# Final_Bread_Proofing_Box_2020_05_10_A.net
KiCad netlist of a schematic drawn in EAGLE
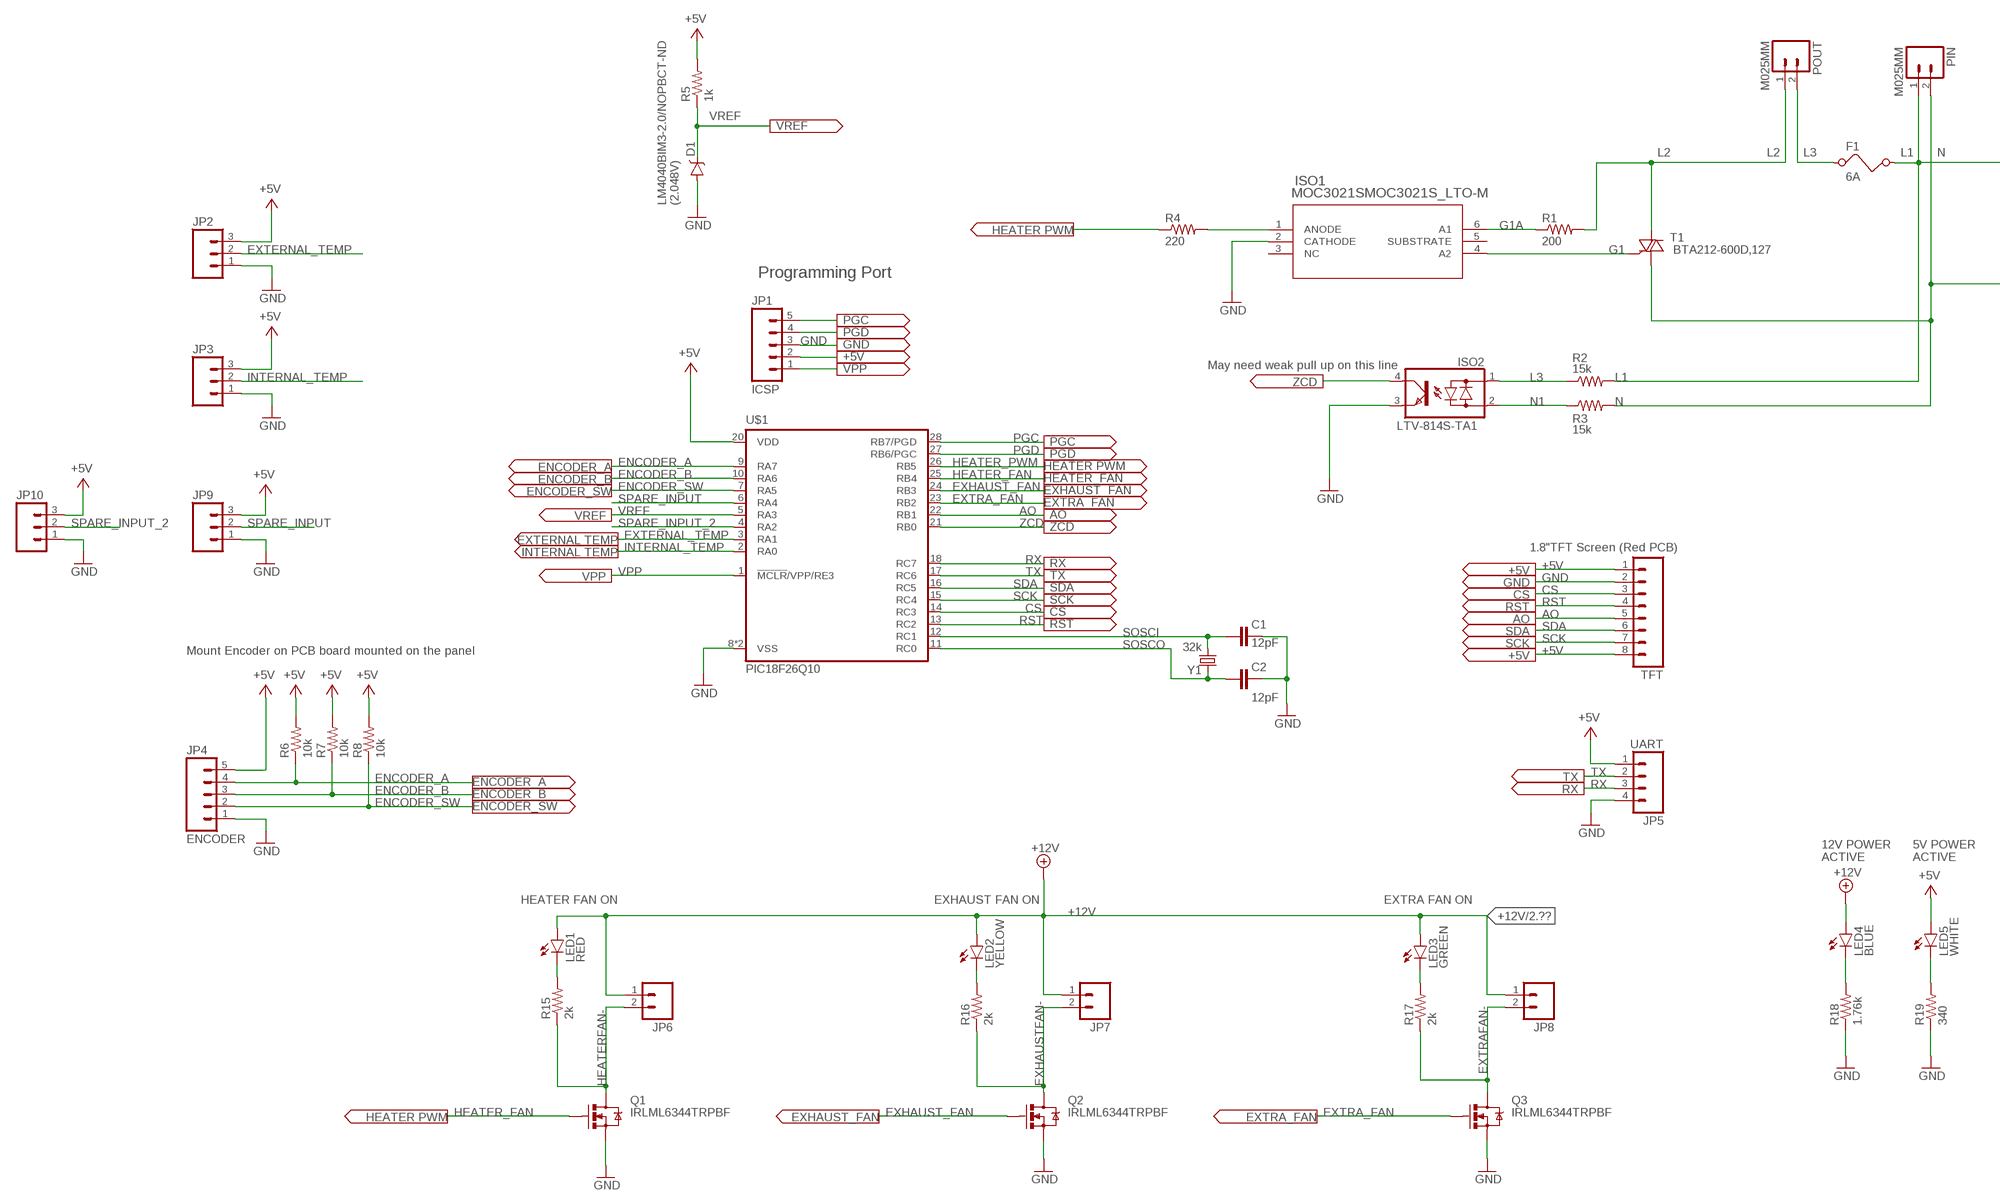
[diagram p0: schematic, sheet 1, part 1 of 2]
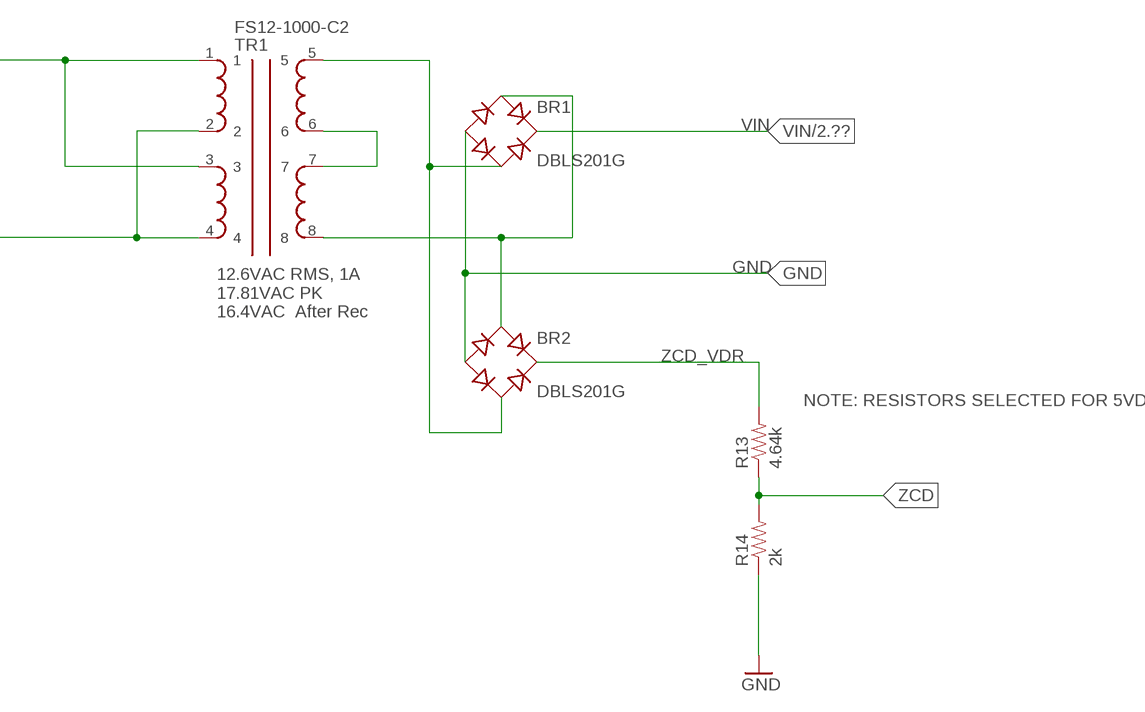
[diagram p1: schematic, sheet 1, part 2 of 2]
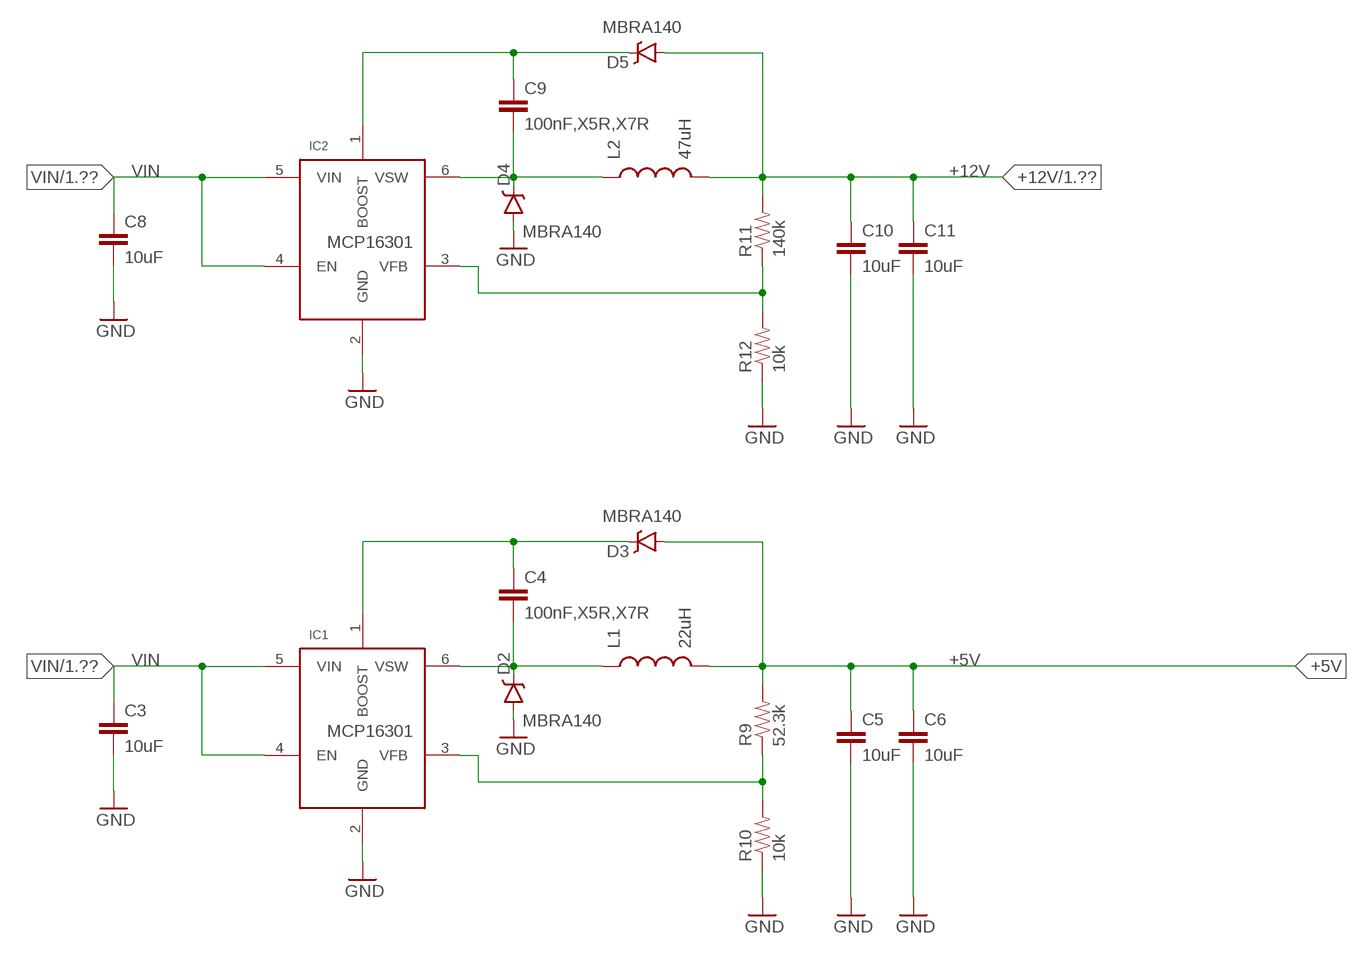
[diagram p2: schematic, sheet 2]

(export (version "E")
  (design (tool "Eeschema 10.0.6"))
  (components
    (comp (ref "C3")
      (value "10uF")
      (footprint "eagle-import:1206")
      (libsource (lib "eagle-import") (part "CAP1206"))
    )
    (comp (ref "C4")
      (value "100nF,X5R,X7R")
      (footprint "eagle-import:1206")
      (libsource (lib "eagle-import") (part "CAP1206"))
    )
    (comp (ref "C5")
      (value "10uF")
      (footprint "eagle-import:1206")
      (libsource (lib "eagle-import") (part "CAP1206"))
    )
    (comp (ref "C6")
      (value "10uF")
      (footprint "eagle-import:1206")
      (libsource (lib "eagle-import") (part "CAP1206"))
    )
    (comp (ref "C8")
      (value "10uF")
      (footprint "eagle-import:1206")
      (libsource (lib "eagle-import") (part "CAP1206"))
    )
    (comp (ref "C9")
      (value "100nF,X5R,X7R")
      (footprint "eagle-import:1206")
      (libsource (lib "eagle-import") (part "CAP1206"))
    )
    (comp (ref "C10")
      (value "10uF")
      (footprint "eagle-import:1206")
      (libsource (lib "eagle-import") (part "CAP1206"))
    )
    (comp (ref "C11")
      (value "10uF")
      (footprint "eagle-import:1206")
      (libsource (lib "eagle-import") (part "CAP1206"))
    )
    (comp (ref "D2")
      (value "MBRA140")
      (footprint "eagle-import:SMA-DIODE")
      (libsource (lib "eagle-import") (part "DIODE-SCHOTTKY-MBRA140"))
    )
    (comp (ref "D3")
      (value "MBRA140")
      (footprint "eagle-import:SMA-DIODE")
      (libsource (lib "eagle-import") (part "DIODE-SCHOTTKY-MBRA140"))
    )
    (comp (ref "D4")
      (value "MBRA140")
      (footprint "eagle-import:SMA-DIODE")
      (libsource (lib "eagle-import") (part "DIODE-SCHOTTKY-MBRA140"))
    )
    (comp (ref "D5")
      (value "MBRA140")
      (footprint "eagle-import:SMA-DIODE")
      (libsource (lib "eagle-import") (part "DIODE-SCHOTTKY-MBRA140"))
    )
    (comp (ref "IC1")
      (value "MCP16301")
      (footprint "eagle-import:SOT23-6")
      (libsource (lib "eagle-import") (part "MCP16301"))
    )
    (comp (ref "IC2")
      (value "MCP16301")
      (footprint "eagle-import:SOT23-6")
      (libsource (lib "eagle-import") (part "MCP16301"))
    )
    (comp (ref "L1")
      (value "22uH")
      (footprint "eagle-import:1210")
      (libsource (lib "eagle-import") (part "INDUCTOR1210"))
    )
    (comp (ref "L2")
      (value "47uH")
      (footprint "eagle-import:1210")
      (libsource (lib "eagle-import") (part "INDUCTOR1210"))
    )
    (comp (ref "R9")
      (value "52.3k")
      (footprint "eagle-import:1206")
      (libsource (lib "eagle-import") (part "RESISTOR1206"))
    )
    (comp (ref "R10")
      (value "10k")
      (footprint "eagle-import:1206")
      (libsource (lib "eagle-import") (part "RESISTOR1206"))
    )
    (comp (ref "R11")
      (value "140k")
      (footprint "eagle-import:1206")
      (libsource (lib "eagle-import") (part "RESISTOR1206"))
    )
    (comp (ref "R12")
      (value "10k")
      (footprint "eagle-import:1206")
      (libsource (lib "eagle-import") (part "RESISTOR1206"))
    )
    (comp (ref "BR1")
      (value "DBLS201G")
      (footprint "eagle-import:DBS")
      (libsource (lib "eagle-import") (part "DB?GLS201"))
    )
    (comp (ref "BR2")
      (value "DBLS201G")
      (footprint "eagle-import:DBS")
      (libsource (lib "eagle-import") (part "DB?GLS201"))
    )
    (comp (ref "C1")
      (value "12pF")
      (footprint "eagle-import:0805")
      (libsource (lib "eagle-import") (part "CAP0805"))
    )
    (comp (ref "C2")
      (value "12pF")
      (footprint "eagle-import:0805")
      (libsource (lib "eagle-import") (part "CAP0805"))
    )
    (comp (ref "D1")
      (value "V-REFERENCESMD")
      (footprint "eagle-import:SOT23-3")
      (libsource (lib "eagle-import") (part "V-REFERENCESMD"))
    )
    (comp (ref "F1")
      (value "6A")
      (footprint "eagle-import:FUSE")
      (libsource (lib "eagle-import") (part "FUSE"))
    )
    (comp (ref "ISO1")
      (value "MOC3021SMOC3021S_LTO-M")
      (footprint "eagle-import:MOC3021S_LTO-M")
      (fields
        (field (name "MANUFACTURER_PART_NUMBER") "MOC3021S")
        (field (name "COPYRIGHT") "Copyright (C) 2018 Accelerated Designs. All rights reserved")
      )
      (libsource (lib "eagle-import") (part "MOC3021SMOC3021S_LTO-M"))
    )
    (comp (ref "ISO2")
      (value "LTV-814S-TA1")
      (footprint "eagle-import:DIL4-SMD")
      (fields (field (name "MF") "VISHAY/TELEFUNKEN") (field (name "MPN") "SFH6206-3"))
      (libsource (lib "eagle-import") (part "SFH6206"))
    )
    (comp (ref "JP1")
      (value "ICSP")
      (footprint "eagle-import:1X05")
      (libsource (lib "eagle-import") (part "M05PTH"))
    )
    (comp (ref "JP2")
      (value "M03POLAR")
      (footprint "eagle-import:MOLEX-1X3")
      (libsource (lib "eagle-import") (part "M03POLAR"))
    )
    (comp (ref "JP3")
      (value "M03POLAR")
      (footprint "eagle-import:MOLEX-1X3")
      (libsource (lib "eagle-import") (part "M03POLAR"))
    )
    (comp (ref "JP4")
      (value "ENCODER")
      (footprint "eagle-import:1X05")
      (libsource (lib "eagle-import") (part "M05PTH"))
    )
    (comp (ref "JP5")
      (value "UART")
      (footprint "eagle-import:1X04_LOCK")
      (libsource (lib "eagle-import") (part "M04LOCK"))
    )
    (comp (ref "JP6")
      (value "M02POLAR_LOCK")
      (footprint "eagle-import:MOLEX-1X2_LOCK")
      (libsource (lib "eagle-import") (part "M02POLAR_LOCK"))
    )
    (comp (ref "JP7")
      (value "M02POLAR_LOCK")
      (footprint "eagle-import:MOLEX-1X2_LOCK")
      (libsource (lib "eagle-import") (part "M02POLAR_LOCK"))
    )
    (comp (ref "JP8")
      (value "M02POLAR_LOCK")
      (footprint "eagle-import:MOLEX-1X2_LOCK")
      (libsource (lib "eagle-import") (part "M02POLAR_LOCK"))
    )
    (comp (ref "JP9")
      (value "M03POLAR")
      (footprint "eagle-import:MOLEX-1X3")
      (libsource (lib "eagle-import") (part "M03POLAR"))
    )
    (comp (ref "JP10")
      (value "M03POLAR")
      (footprint "eagle-import:MOLEX-1X3")
      (libsource (lib "eagle-import") (part "M03POLAR"))
    )
    (comp (ref "LED1")
      (value "RED")
      (footprint "eagle-import:LED-1206")
      (libsource (lib "eagle-import") (part "LED1206"))
    )
    (comp (ref "LED2")
      (value "YELLOW")
      (footprint "eagle-import:LED-1206")
      (libsource (lib "eagle-import") (part "LED1206"))
    )
    (comp (ref "LED3")
      (value "GREEN")
      (footprint "eagle-import:LED-1206")
      (libsource (lib "eagle-import") (part "LED1206"))
    )
    (comp (ref "LED4")
      (value "BLUE")
      (footprint "eagle-import:LED-1206")
      (libsource (lib "eagle-import") (part "LED1206"))
    )
    (comp (ref "LED5")
      (value "WHITE")
      (footprint "eagle-import:LED-1206")
      (libsource (lib "eagle-import") (part "LED1206"))
    )
    (comp (ref "PIN")
      (value "M025MM")
      (footprint "eagle-import:SCREWTERMINAL-5MM-2")
      (libsource (lib "eagle-import") (part "M025MM"))
    )
    (comp (ref "POUT")
      (value "M025MM")
      (footprint "eagle-import:SCREWTERMINAL-5MM-2")
      (libsource (lib "eagle-import") (part "M025MM"))
    )
    (comp (ref "Q1")
      (value "IRLML6344TRPBF")
      (footprint "eagle-import:SOT323")
      (libsource (lib "eagle-import") (part "MOSFET-NCHANNEL2N7002PW"))
    )
    (comp (ref "Q2")
      (value "IRLML6344TRPBF")
      (footprint "eagle-import:SOT323")
      (libsource (lib "eagle-import") (part "MOSFET-NCHANNEL2N7002PW"))
    )
    (comp (ref "Q3")
      (value "IRLML6344TRPBF")
      (footprint "eagle-import:SOT323")
      (libsource (lib "eagle-import") (part "MOSFET-NCHANNEL2N7002PW"))
    )
    (comp (ref "R1")
      (value "200")
      (footprint "eagle-import:R2512")
      (libsource (lib "eagle-import") (part "R-US_R2512"))
    )
    (comp (ref "R2")
      (value "15k")
      (footprint "eagle-import:R2512")
      (libsource (lib "eagle-import") (part "R-US_R2512"))
    )
    (comp (ref "R3")
      (value "15k")
      (footprint "eagle-import:R2512")
      (libsource (lib "eagle-import") (part "R-US_R2512"))
    )
    (comp (ref "R4")
      (value "220")
      (footprint "eagle-import:1206")
      (libsource (lib "eagle-import") (part "RESISTOR1206"))
    )
    (comp (ref "R5")
      (value "1k")
      (footprint "eagle-import:1206")
      (libsource (lib "eagle-import") (part "RESISTOR1206"))
    )
    (comp (ref "R6")
      (value "10k")
      (footprint "eagle-import:1206")
      (libsource (lib "eagle-import") (part "RESISTOR1206"))
    )
    (comp (ref "R7")
      (value "10k")
      (footprint "eagle-import:1206")
      (libsource (lib "eagle-import") (part "RESISTOR1206"))
    )
    (comp (ref "R8")
      (value "10k")
      (footprint "eagle-import:1206")
      (libsource (lib "eagle-import") (part "RESISTOR1206"))
    )
    (comp (ref "R13")
      (value "4.64k")
      (footprint "eagle-import:1206")
      (libsource (lib "eagle-import") (part "RESISTOR1206"))
    )
    (comp (ref "R14")
      (value "2k")
      (footprint "eagle-import:1206")
      (libsource (lib "eagle-import") (part "RESISTOR1206"))
    )
    (comp (ref "R15")
      (value "2k")
      (footprint "eagle-import:1206")
      (libsource (lib "eagle-import") (part "RESISTOR1206"))
    )
    (comp (ref "R16")
      (value "2k")
      (footprint "eagle-import:1206")
      (libsource (lib "eagle-import") (part "RESISTOR1206"))
    )
    (comp (ref "R17")
      (value "2k")
      (footprint "eagle-import:1206")
      (libsource (lib "eagle-import") (part "RESISTOR1206"))
    )
    (comp (ref "R18")
      (value "1.76k")
      (footprint "eagle-import:1206")
      (libsource (lib "eagle-import") (part "RESISTOR1206"))
    )
    (comp (ref "R19")
      (value "340")
      (footprint "eagle-import:1206")
      (libsource (lib "eagle-import") (part "RESISTOR1206"))
    )
    (comp (ref "T1")
      (value "BTA212-600D,127")
      (footprint "eagle-import:TO220BV")
      (libsource (lib "eagle-import") (part "BT138-V"))
    )
    (comp (ref "TFT")
      (value "M08LOCK")
      (footprint "eagle-import:1X08_LOCK")
      (libsource (lib "eagle-import") (part "M08LOCK"))
    )
    (comp (ref "TR1")
      (value "FS12-1000-C2")
      (footprint "eagle-import:FS12-1000-C2")
      (libsource (lib "eagle-import") (part "FS12-1000-C2"))
    )
    (comp (ref "U$1")
      (value "PIC18F26Q10")
      (footprint "eagle-import:SO28W")
      (libsource (lib "eagle-import") (part "PIC18F25K22SOIC"))
    )
    (comp (ref "Y1")
      (value "32k")
      (footprint "eagle-import:TC26V")
      (libsource (lib "eagle-import") (part "CRYSTALTC26V"))
    )
  )
  (nets
    (net (code "1") (name "+5V") (class "Default")
      (node (ref "C5") (pin "1") (pinfunction "1_1") (pintype "passive"))
      (node (ref "C6") (pin "1") (pinfunction "1_1") (pintype "passive"))
      (node (ref "D3") (pin "A") (pinfunction "A_A") (pintype "passive"))
      (node (ref "JP1") (pin "2") (pinfunction "2_2") (pintype "passive"))
      (node (ref "JP10") (pin "3") (pinfunction "3_3") (pintype "passive"))
      (node (ref "JP2") (pin "3") (pinfunction "3_3") (pintype "passive"))
      (node (ref "JP3") (pin "3") (pinfunction "3_3") (pintype "passive"))
      (node (ref "JP4") (pin "5") (pinfunction "5_5") (pintype "passive"))
      (node (ref "JP5") (pin "1") (pinfunction "1_1") (pintype "passive"))
      (node (ref "JP9") (pin "3") (pinfunction "3_3") (pintype "passive"))
      (node (ref "L1") (pin "2") (pinfunction "2_2") (pintype "passive"))
      (node (ref "LED5") (pin "A") (pinfunction "A_A") (pintype "passive"))
      (node (ref "R5") (pin "2") (pinfunction "2_2") (pintype "passive"))
      (node (ref "R6") (pin "2") (pinfunction "2_2") (pintype "passive"))
      (node (ref "R7") (pin "2") (pinfunction "2_2") (pintype "passive"))
      (node (ref "R8") (pin "2") (pinfunction "2_2") (pintype "passive"))
      (node (ref "R9") (pin "2") (pinfunction "2_2") (pintype "passive"))
      (node (ref "TFT") (pin "1") (pinfunction "1_1") (pintype "passive"))
      (node (ref "TFT") (pin "8") (pinfunction "8_8") (pintype "passive"))
      (node (ref "U$1") (pin "20") (pinfunction "VDD_20") (pintype "power_in"))
    )
    (net (code "2") (name "+12V") (class "Default")
      (node (ref "C10") (pin "1") (pinfunction "1_1") (pintype "passive"))
      (node (ref "C11") (pin "1") (pinfunction "1_1") (pintype "passive"))
      (node (ref "D5") (pin "A") (pinfunction "A_A") (pintype "passive"))
      (node (ref "JP6") (pin "1") (pinfunction "1_1") (pintype "passive"))
      (node (ref "JP7") (pin "1") (pinfunction "1_1") (pintype "passive"))
      (node (ref "JP8") (pin "1") (pinfunction "1_1") (pintype "passive"))
      (node (ref "L2") (pin "2") (pinfunction "2_2") (pintype "passive"))
      (node (ref "LED1") (pin "A") (pinfunction "A_A") (pintype "passive"))
      (node (ref "LED2") (pin "A") (pinfunction "A_A") (pintype "passive"))
      (node (ref "LED3") (pin "A") (pinfunction "A_A") (pintype "passive"))
      (node (ref "LED4") (pin "A") (pinfunction "A_A") (pintype "passive"))
      (node (ref "R11") (pin "2") (pinfunction "2_2") (pintype "passive"))
    )
    (net (code "3") (name "AO") (class "Default")
      (node (ref "TFT") (pin "5") (pinfunction "5_5") (pintype "passive"))
      (node (ref "U$1") (pin "22") (pinfunction "RB1_22") (pintype "bidirectional"))
    )
    (net (code "4") (name "CS") (class "Default")
      (node (ref "TFT") (pin "3") (pinfunction "3_3") (pintype "passive"))
      (node (ref "U$1") (pin "14") (pinfunction "RC3_14") (pintype "bidirectional"))
    )
    (net (code "5") (name "ENCODER_A") (class "Default")
      (node (ref "JP4") (pin "4") (pinfunction "4_4") (pintype "passive"))
      (node (ref "R6") (pin "1") (pinfunction "1_1") (pintype "passive"))
      (node (ref "U$1") (pin "9") (pinfunction "RA7_9") (pintype "bidirectional"))
    )
    (net (code "6") (name "ENCODER_B") (class "Default")
      (node (ref "JP4") (pin "3") (pinfunction "3_3") (pintype "passive"))
      (node (ref "R7") (pin "1") (pinfunction "1_1") (pintype "passive"))
      (node (ref "U$1") (pin "10") (pinfunction "RA6_10") (pintype "bidirectional"))
    )
    (net (code "7") (name "ENCODER_SW") (class "Default")
      (node (ref "JP4") (pin "2") (pinfunction "2_2") (pintype "passive"))
      (node (ref "R8") (pin "1") (pinfunction "1_1") (pintype "passive"))
      (node (ref "U$1") (pin "7") (pinfunction "RA5_7") (pintype "bidirectional"))
    )
    (net (code "8") (name "EXHAUSTFAN-") (class "Default")
      (node (ref "JP7") (pin "2") (pinfunction "2_2") (pintype "passive"))
      (node (ref "Q2") (pin "3") (pinfunction "D_3") (pintype "passive"))
      (node (ref "R16") (pin "1") (pinfunction "1_1") (pintype "passive"))
    )
    (net (code "9") (name "EXHAUST_FAN") (class "Default")
      (node (ref "Q2") (pin "1") (pinfunction "G_1") (pintype "passive"))
      (node (ref "U$1") (pin "24") (pinfunction "RB3_24") (pintype "bidirectional"))
    )
    (net (code "10") (name "EXTERNAL_TEMP") (class "Default")
      (node (ref "JP2") (pin "2") (pinfunction "2_2") (pintype "passive"))
      (node (ref "U$1") (pin "3") (pinfunction "RA1_3") (pintype "bidirectional"))
    )
    (net (code "11") (name "EXTRAFAN-") (class "Default")
      (node (ref "JP8") (pin "2") (pinfunction "2_2") (pintype "passive"))
      (node (ref "Q3") (pin "3") (pinfunction "D_3") (pintype "passive"))
      (node (ref "R17") (pin "1") (pinfunction "1_1") (pintype "passive"))
    )
    (net (code "12") (name "EXTRA_FAN") (class "Default")
      (node (ref "Q3") (pin "1") (pinfunction "G_1") (pintype "passive"))
      (node (ref "U$1") (pin "23") (pinfunction "RB2_23") (pintype "bidirectional"))
    )
    (net (code "13") (name "G1") (class "Default")
      (node (ref "ISO1") (pin "4") (pinfunction "A2_4") (pintype "passive"))
      (node (ref "T1") (pin "G") (pinfunction "G_G") (pintype "passive"))
    )
    (net (code "14") (name "G1A") (class "Default")
      (node (ref "ISO1") (pin "6") (pinfunction "A1_6") (pintype "passive"))
      (node (ref "R1") (pin "1") (pinfunction "1_1") (pintype "passive"))
    )
    (net (code "15") (name "GND") (class "Default")
      (node (ref "BR1") (pin "-") (pinfunction "-_-") (pintype "passive"))
      (node (ref "BR2") (pin "-") (pinfunction "-_-") (pintype "passive"))
      (node (ref "C1") (pin "2") (pinfunction "2_2") (pintype "passive"))
      (node (ref "C10") (pin "2") (pinfunction "2_2") (pintype "passive"))
      (node (ref "C11") (pin "2") (pinfunction "2_2") (pintype "passive"))
      (node (ref "C2") (pin "2") (pinfunction "2_2") (pintype "passive"))
      (node (ref "C3") (pin "2") (pinfunction "2_2") (pintype "passive"))
      (node (ref "C5") (pin "2") (pinfunction "2_2") (pintype "passive"))
      (node (ref "C6") (pin "2") (pinfunction "2_2") (pintype "passive"))
      (node (ref "C8") (pin "2") (pinfunction "2_2") (pintype "passive"))
      (node (ref "D1") (pin "2") (pinfunction "A_2") (pintype "passive"))
      (node (ref "D2") (pin "A") (pinfunction "A_A") (pintype "passive"))
      (node (ref "D4") (pin "A") (pinfunction "A_A") (pintype "passive"))
      (node (ref "IC1") (pin "2") (pinfunction "GND_2") (pintype "bidirectional"))
      (node (ref "IC2") (pin "2") (pinfunction "GND_2") (pintype "bidirectional"))
      (node (ref "ISO1") (pin "2") (pinfunction "CATHODE_2") (pintype "passive"))
      (node (ref "ISO2") (pin "3") (pinfunction "E_3") (pintype "passive"))
      (node (ref "JP1") (pin "3") (pinfunction "3_3") (pintype "passive"))
      (node (ref "JP10") (pin "1") (pinfunction "1_1") (pintype "passive"))
      (node (ref "JP2") (pin "1") (pinfunction "1_1") (pintype "passive"))
      (node (ref "JP3") (pin "1") (pinfunction "1_1") (pintype "passive"))
      (node (ref "JP4") (pin "1") (pinfunction "1_1") (pintype "passive"))
      (node (ref "JP5") (pin "4") (pinfunction "4_4") (pintype "passive"))
      (node (ref "JP9") (pin "1") (pinfunction "1_1") (pintype "passive"))
      (node (ref "Q1") (pin "2") (pinfunction "S_2") (pintype "passive"))
      (node (ref "Q2") (pin "2") (pinfunction "S_2") (pintype "passive"))
      (node (ref "Q3") (pin "2") (pinfunction "S_2") (pintype "passive"))
      (node (ref "R10") (pin "1") (pinfunction "1_1") (pintype "passive"))
      (node (ref "R12") (pin "1") (pinfunction "1_1") (pintype "passive"))
      (node (ref "R14") (pin "1") (pinfunction "1_1") (pintype "passive"))
      (node (ref "R18") (pin "1") (pinfunction "1_1") (pintype "passive"))
      (node (ref "R19") (pin "1") (pinfunction "1_1") (pintype "passive"))
      (node (ref "TFT") (pin "2") (pinfunction "2_2") (pintype "passive"))
      (node (ref "U$1") (pin "19") (pinfunction "VSS_19") (pintype "power_in"))
      (node (ref "U$1") (pin "8") (pinfunction "VSS_8") (pintype "power_in"))
    )
    (net (code "16") (name "HEATERFAN-") (class "Default")
      (node (ref "JP6") (pin "2") (pinfunction "2_2") (pintype "passive"))
      (node (ref "Q1") (pin "3") (pinfunction "D_3") (pintype "passive"))
      (node (ref "R15") (pin "1") (pinfunction "1_1") (pintype "passive"))
    )
    (net (code "17") (name "HEATER_FAN") (class "Default")
      (node (ref "Q1") (pin "1") (pinfunction "G_1") (pintype "passive"))
      (node (ref "U$1") (pin "25") (pinfunction "RB4_25") (pintype "bidirectional"))
    )
    (net (code "18") (name "HEATER_PWM") (class "Default")
      (node (ref "R4") (pin "1") (pinfunction "1_1") (pintype "passive"))
      (node (ref "U$1") (pin "26") (pinfunction "RB5_26") (pintype "bidirectional"))
    )
    (net (code "19") (name "INTERNAL_TEMP") (class "Default")
      (node (ref "JP3") (pin "2") (pinfunction "2_2") (pintype "passive"))
      (node (ref "U$1") (pin "2") (pinfunction "RA0_2") (pintype "bidirectional"))
    )
    (net (code "20") (name "L1") (class "Default")
      (node (ref "F1") (pin "2") (pinfunction "2_2") (pintype "passive"))
      (node (ref "PIN") (pin "1") (pinfunction "1_1") (pintype "passive"))
      (node (ref "R2") (pin "2") (pinfunction "2_2") (pintype "passive"))
      (node (ref "TR1") (pin "1") (pinfunction "1_1") (pintype "passive"))
      (node (ref "TR1") (pin "3") (pinfunction "3_3") (pintype "passive"))
    )
    (net (code "21") (name "L2") (class "Default")
      (node (ref "POUT") (pin "1") (pinfunction "1_1") (pintype "passive"))
      (node (ref "R1") (pin "2") (pinfunction "2_2") (pintype "passive"))
      (node (ref "T1") (pin "T2") (pinfunction "A2_T2") (pintype "passive"))
    )
    (net (code "22") (name "L3") (class "Default")
      (node (ref "F1") (pin "1") (pinfunction "1_1") (pintype "passive"))
      (node (ref "ISO2") (pin "1") (pinfunction "AC1_1") (pintype "passive"))
      (node (ref "POUT") (pin "2") (pinfunction "2_2") (pintype "passive"))
      (node (ref "R2") (pin "1") (pinfunction "1_1") (pintype "passive"))
    )
    (net (code "23") (name "N") (class "Default")
      (node (ref "PIN") (pin "2") (pinfunction "2_2") (pintype "passive"))
      (node (ref "R3") (pin "2") (pinfunction "2_2") (pintype "passive"))
      (node (ref "T1") (pin "T1") (pinfunction "A1_T1") (pintype "passive"))
      (node (ref "TR1") (pin "2") (pinfunction "2_2") (pintype "passive"))
      (node (ref "TR1") (pin "4") (pinfunction "4_4") (pintype "passive"))
    )
    (net (code "24") (name "N1") (class "Default")
      (node (ref "ISO2") (pin "2") (pinfunction "AC2_2") (pintype "passive"))
      (node (ref "R3") (pin "1") (pinfunction "1_1") (pintype "passive"))
    )
    (net (code "25") (name "Net-(BR1-PadAC1)") (class "Default")
      (node (ref "BR1") (pin "AC1") (pinfunction "AC1_AC1") (pintype "passive"))
      (node (ref "BR2") (pin "AC1") (pinfunction "AC1_AC1") (pintype "passive"))
      (node (ref "TR1") (pin "8") (pinfunction "8_8") (pintype "bidirectional"))
    )
    (net (code "26") (name "Net-(BR1-PadAC2)") (class "Default")
      (node (ref "BR1") (pin "AC2") (pinfunction "AC2_AC2") (pintype "passive"))
      (node (ref "BR2") (pin "AC2") (pinfunction "AC2_AC2") (pintype "passive"))
      (node (ref "TR1") (pin "5") (pinfunction "5_5") (pintype "bidirectional"))
    )
    (net (code "27") (name "Net-(IC1-BOOST)") (class "Default")
      (node (ref "C4") (pin "1") (pinfunction "1_1") (pintype "passive"))
      (node (ref "D3") (pin "C") (pinfunction "C_C") (pintype "passive"))
      (node (ref "IC1") (pin "1") (pinfunction "BOOST_1") (pintype "bidirectional"))
    )
    (net (code "28") (name "Net-(IC1-VFB)") (class "Default")
      (node (ref "IC1") (pin "3") (pinfunction "VFB_3") (pintype "bidirectional"))
      (node (ref "R10") (pin "2") (pinfunction "2_2") (pintype "passive"))
      (node (ref "R9") (pin "1") (pinfunction "1_1") (pintype "passive"))
    )
    (net (code "29") (name "Net-(IC1-VSW)") (class "Default")
      (node (ref "C4") (pin "2") (pinfunction "2_2") (pintype "passive"))
      (node (ref "D2") (pin "C") (pinfunction "C_C") (pintype "passive"))
      (node (ref "IC1") (pin "6") (pinfunction "VSW_6") (pintype "bidirectional"))
      (node (ref "L1") (pin "1") (pinfunction "1_1") (pintype "passive"))
    )
    (net (code "30") (name "Net-(IC2-BOOST)") (class "Default")
      (node (ref "C9") (pin "1") (pinfunction "1_1") (pintype "passive"))
      (node (ref "D5") (pin "C") (pinfunction "C_C") (pintype "passive"))
      (node (ref "IC2") (pin "1") (pinfunction "BOOST_1") (pintype "bidirectional"))
    )
    (net (code "31") (name "Net-(IC2-VFB)") (class "Default")
      (node (ref "IC2") (pin "3") (pinfunction "VFB_3") (pintype "bidirectional"))
      (node (ref "R11") (pin "1") (pinfunction "1_1") (pintype "passive"))
      (node (ref "R12") (pin "2") (pinfunction "2_2") (pintype "passive"))
    )
    (net (code "32") (name "Net-(IC2-VSW)") (class "Default")
      (node (ref "C9") (pin "2") (pinfunction "2_2") (pintype "passive"))
      (node (ref "D4") (pin "C") (pinfunction "C_C") (pintype "passive"))
      (node (ref "IC2") (pin "6") (pinfunction "VSW_6") (pintype "bidirectional"))
      (node (ref "L2") (pin "1") (pinfunction "1_1") (pintype "passive"))
    )
    (net (code "33") (name "Net-(ISO1-ANODE)") (class "Default")
      (node (ref "ISO1") (pin "1") (pinfunction "ANODE_1") (pintype "passive"))
      (node (ref "R4") (pin "2") (pinfunction "2_2") (pintype "passive"))
    )
    (net (code "34") (name "Net-(LED1-PadC)") (class "Default")
      (node (ref "LED1") (pin "C") (pinfunction "C_C") (pintype "passive"))
      (node (ref "R15") (pin "2") (pinfunction "2_2") (pintype "passive"))
    )
    (net (code "35") (name "Net-(LED2-PadC)") (class "Default")
      (node (ref "LED2") (pin "C") (pinfunction "C_C") (pintype "passive"))
      (node (ref "R16") (pin "2") (pinfunction "2_2") (pintype "passive"))
    )
    (net (code "36") (name "Net-(LED3-PadC)") (class "Default")
      (node (ref "LED3") (pin "C") (pinfunction "C_C") (pintype "passive"))
      (node (ref "R17") (pin "2") (pinfunction "2_2") (pintype "passive"))
    )
    (net (code "37") (name "Net-(LED4-PadC)") (class "Default")
      (node (ref "LED4") (pin "C") (pinfunction "C_C") (pintype "passive"))
      (node (ref "R18") (pin "2") (pinfunction "2_2") (pintype "passive"))
    )
    (net (code "38") (name "Net-(LED5-PadC)") (class "Default")
      (node (ref "LED5") (pin "C") (pinfunction "C_C") (pintype "passive"))
      (node (ref "R19") (pin "2") (pinfunction "2_2") (pintype "passive"))
    )
    (net (code "39") (name "Net-(TR1-Pad6)") (class "Default")
      (node (ref "TR1") (pin "6") (pinfunction "6_6") (pintype "bidirectional"))
      (node (ref "TR1") (pin "7") (pinfunction "7_7") (pintype "bidirectional"))
    )
    (net (code "40") (name "PGC") (class "Default")
      (node (ref "JP1") (pin "5") (pinfunction "5_5") (pintype "passive"))
      (node (ref "U$1") (pin "28") (pinfunction "RB7/PGD_28") (pintype "bidirectional"))
    )
    (net (code "41") (name "PGD") (class "Default")
      (node (ref "JP1") (pin "4") (pinfunction "4_4") (pintype "passive"))
      (node (ref "U$1") (pin "27") (pinfunction "RB6/PGC_27") (pintype "bidirectional"))
    )
    (net (code "42") (name "RST") (class "Default")
      (node (ref "TFT") (pin "4") (pinfunction "4_4") (pintype "passive"))
      (node (ref "U$1") (pin "13") (pinfunction "RC2_13") (pintype "bidirectional"))
    )
    (net (code "43") (name "RX") (class "Default")
      (node (ref "JP5") (pin "3") (pinfunction "3_3") (pintype "passive"))
      (node (ref "U$1") (pin "18") (pinfunction "RC7_18") (pintype "bidirectional"))
    )
    (net (code "44") (name "SCK") (class "Default")
      (node (ref "TFT") (pin "7") (pinfunction "7_7") (pintype "passive"))
      (node (ref "U$1") (pin "15") (pinfunction "RC4_15") (pintype "bidirectional"))
    )
    (net (code "45") (name "SDA") (class "Default")
      (node (ref "TFT") (pin "6") (pinfunction "6_6") (pintype "passive"))
      (node (ref "U$1") (pin "16") (pinfunction "RC5_16") (pintype "bidirectional"))
    )
    (net (code "46") (name "SOSCI") (class "Default")
      (node (ref "C1") (pin "1") (pinfunction "1_1") (pintype "passive"))
      (node (ref "U$1") (pin "12") (pinfunction "RC1_12") (pintype "bidirectional"))
      (node (ref "Y1") (pin "1") (pinfunction "1_1") (pintype "passive"))
    )
    (net (code "47") (name "SOSCO") (class "Default")
      (node (ref "C2") (pin "1") (pinfunction "1_1") (pintype "passive"))
      (node (ref "U$1") (pin "11") (pinfunction "RC0_11") (pintype "bidirectional"))
      (node (ref "Y1") (pin "2") (pinfunction "2_2") (pintype "passive"))
    )
    (net (code "48") (name "SPARE_INPUT") (class "Default")
      (node (ref "JP9") (pin "2") (pinfunction "2_2") (pintype "passive"))
      (node (ref "U$1") (pin "6") (pinfunction "RA4_6") (pintype "bidirectional"))
    )
    (net (code "49") (name "SPARE_INPUT_2") (class "Default")
      (node (ref "JP10") (pin "2") (pinfunction "2_2") (pintype "passive"))
      (node (ref "U$1") (pin "4") (pinfunction "RA2_4") (pintype "bidirectional"))
    )
    (net (code "50") (name "TX") (class "Default")
      (node (ref "JP5") (pin "2") (pinfunction "2_2") (pintype "passive"))
      (node (ref "U$1") (pin "17") (pinfunction "RC6_17") (pintype "bidirectional"))
    )
    (net (code "51") (name "VIN") (class "Default")
      (node (ref "BR1") (pin "+") (pinfunction "+_+") (pintype "passive"))
      (node (ref "C3") (pin "1") (pinfunction "1_1") (pintype "passive"))
      (node (ref "C8") (pin "1") (pinfunction "1_1") (pintype "passive"))
      (node (ref "IC1") (pin "4") (pinfunction "EN_4") (pintype "bidirectional"))
      (node (ref "IC1") (pin "5") (pinfunction "VIN_5") (pintype "bidirectional"))
      (node (ref "IC2") (pin "4") (pinfunction "EN_4") (pintype "bidirectional"))
      (node (ref "IC2") (pin "5") (pinfunction "VIN_5") (pintype "bidirectional"))
    )
    (net (code "52") (name "VPP") (class "Default")
      (node (ref "JP1") (pin "1") (pinfunction "1_1") (pintype "passive"))
      (node (ref "U$1") (pin "1") (pinfunction "~{MCLR}/VPP/RE3_1") (pintype "bidirectional"))
    )
    (net (code "53") (name "VREF") (class "Default")
      (node (ref "D1") (pin "1") (pinfunction "C_1") (pintype "passive"))
      (node (ref "R5") (pin "1") (pinfunction "1_1") (pintype "passive"))
      (node (ref "U$1") (pin "5") (pinfunction "RA3_5") (pintype "bidirectional"))
    )
    (net (code "54") (name "ZCD") (class "Default")
      (node (ref "ISO2") (pin "4") (pinfunction "C_4") (pintype "passive"))
      (node (ref "R13") (pin "1") (pinfunction "1_1") (pintype "passive"))
      (node (ref "R14") (pin "2") (pinfunction "2_2") (pintype "passive"))
      (node (ref "U$1") (pin "21") (pinfunction "RB0_21") (pintype "bidirectional"))
    )
    (net (code "55") (name "ZCD_VDR") (class "Default")
      (node (ref "BR2") (pin "+") (pinfunction "+_+") (pintype "passive"))
      (node (ref "R13") (pin "2") (pinfunction "2_2") (pintype "passive"))
    )
    (net (code "56") (name "unconnected-(ISO1-NC-Pad3)") (class "Default")
      (node (ref "ISO1") (pin "3") (pinfunction "NC_3") (pintype "passive"))
    )
    (net (code "57") (name "unconnected-(ISO1-SUBSTRATE-Pad5)") (class "Default")
      (node (ref "ISO1") (pin "5") (pinfunction "SUBSTRATE_5") (pintype "passive"))
    )
  )
)
